# AQ_sensor_MRC.net
KiCad netlist of a schematic drawn in EAGLE
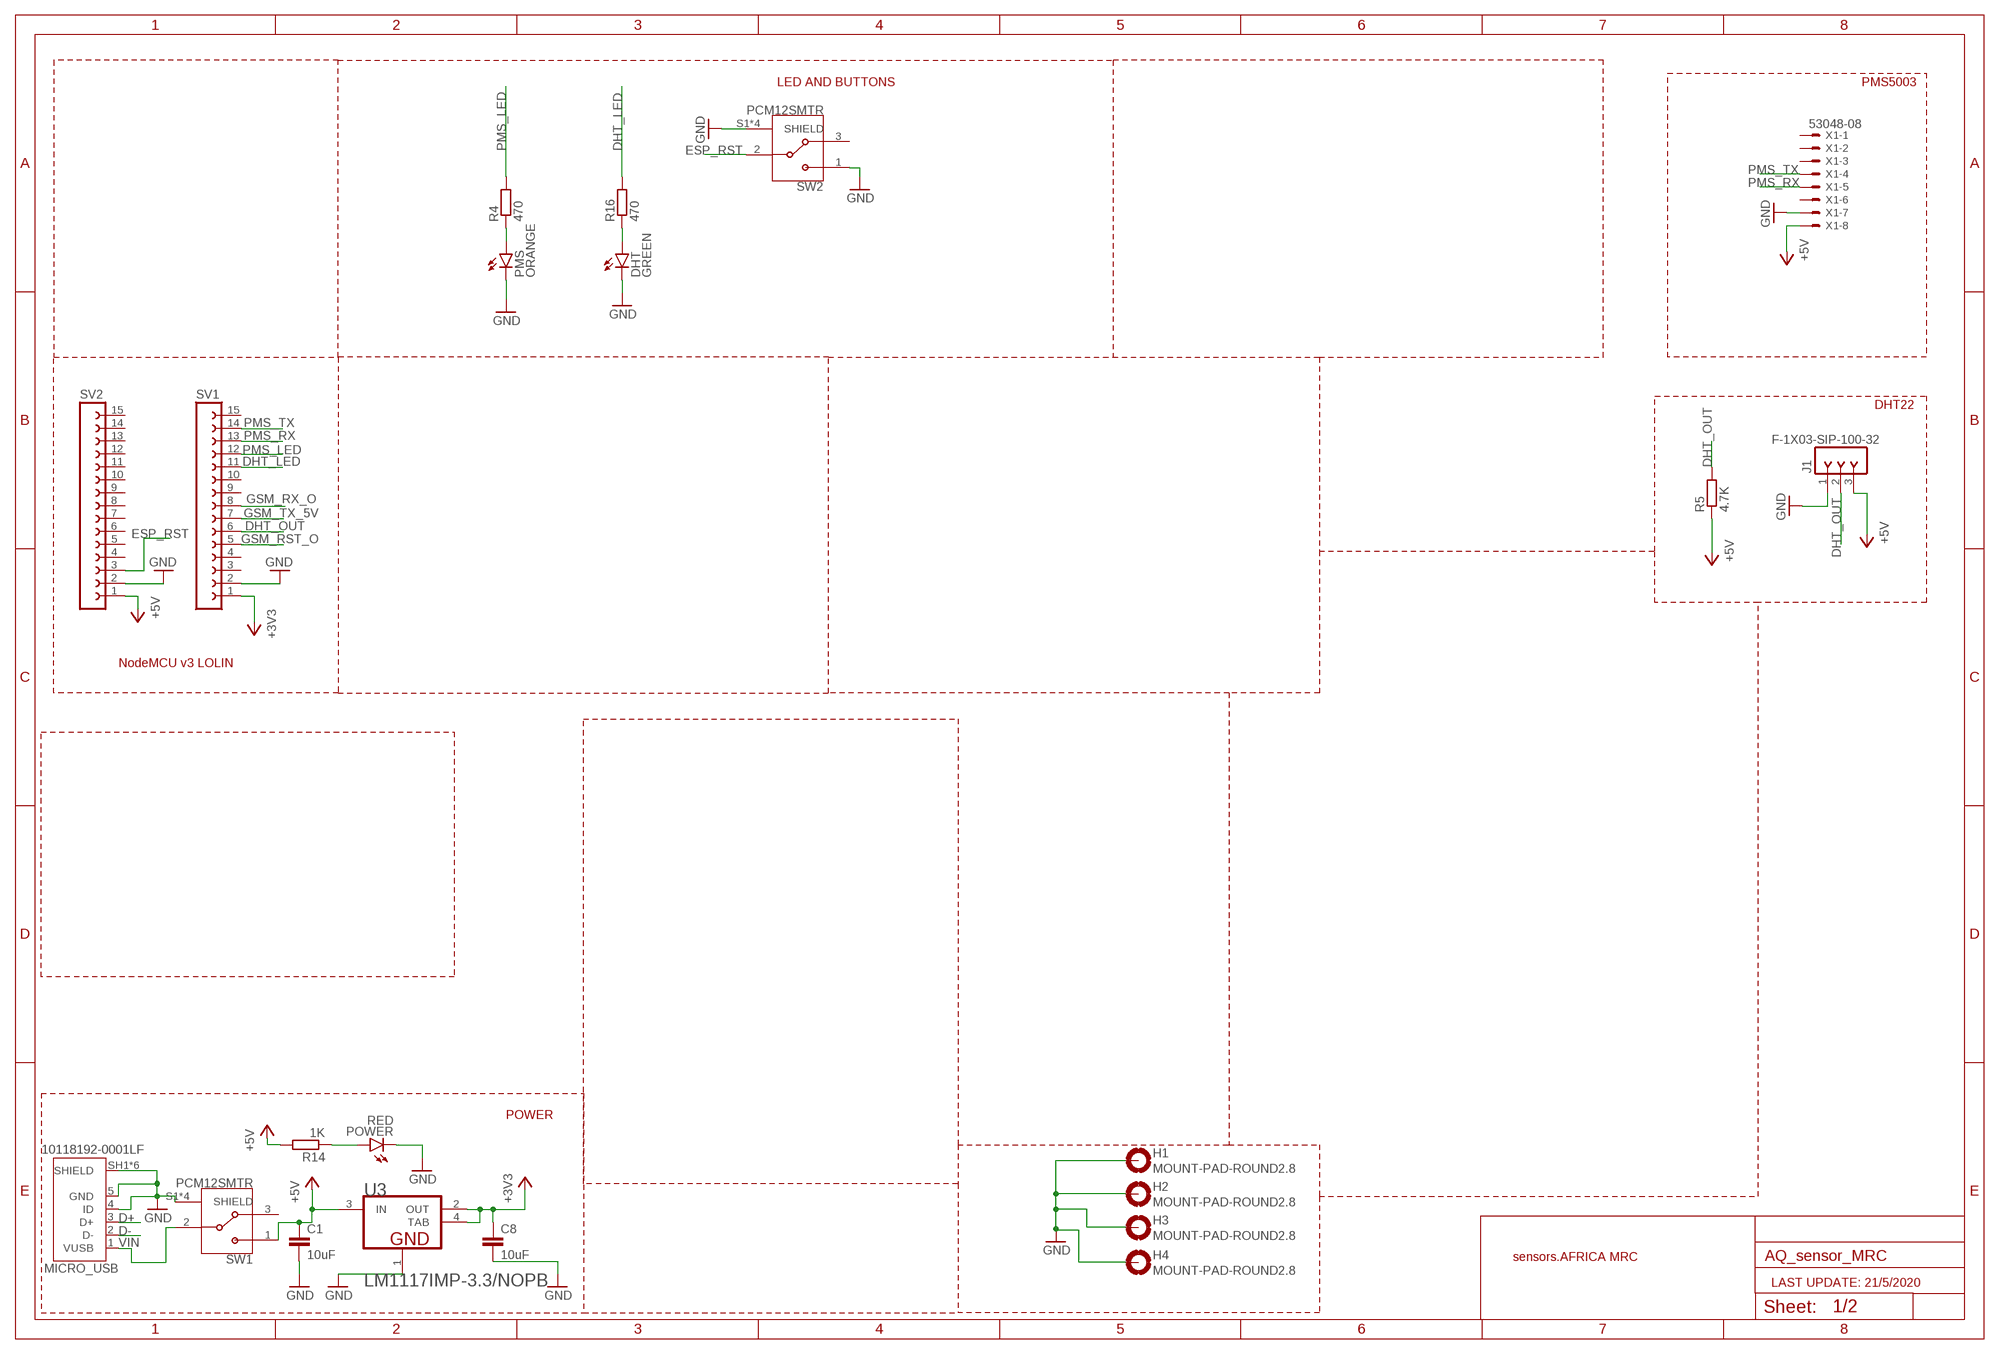
[diagram p0: schematic, sheet 1]
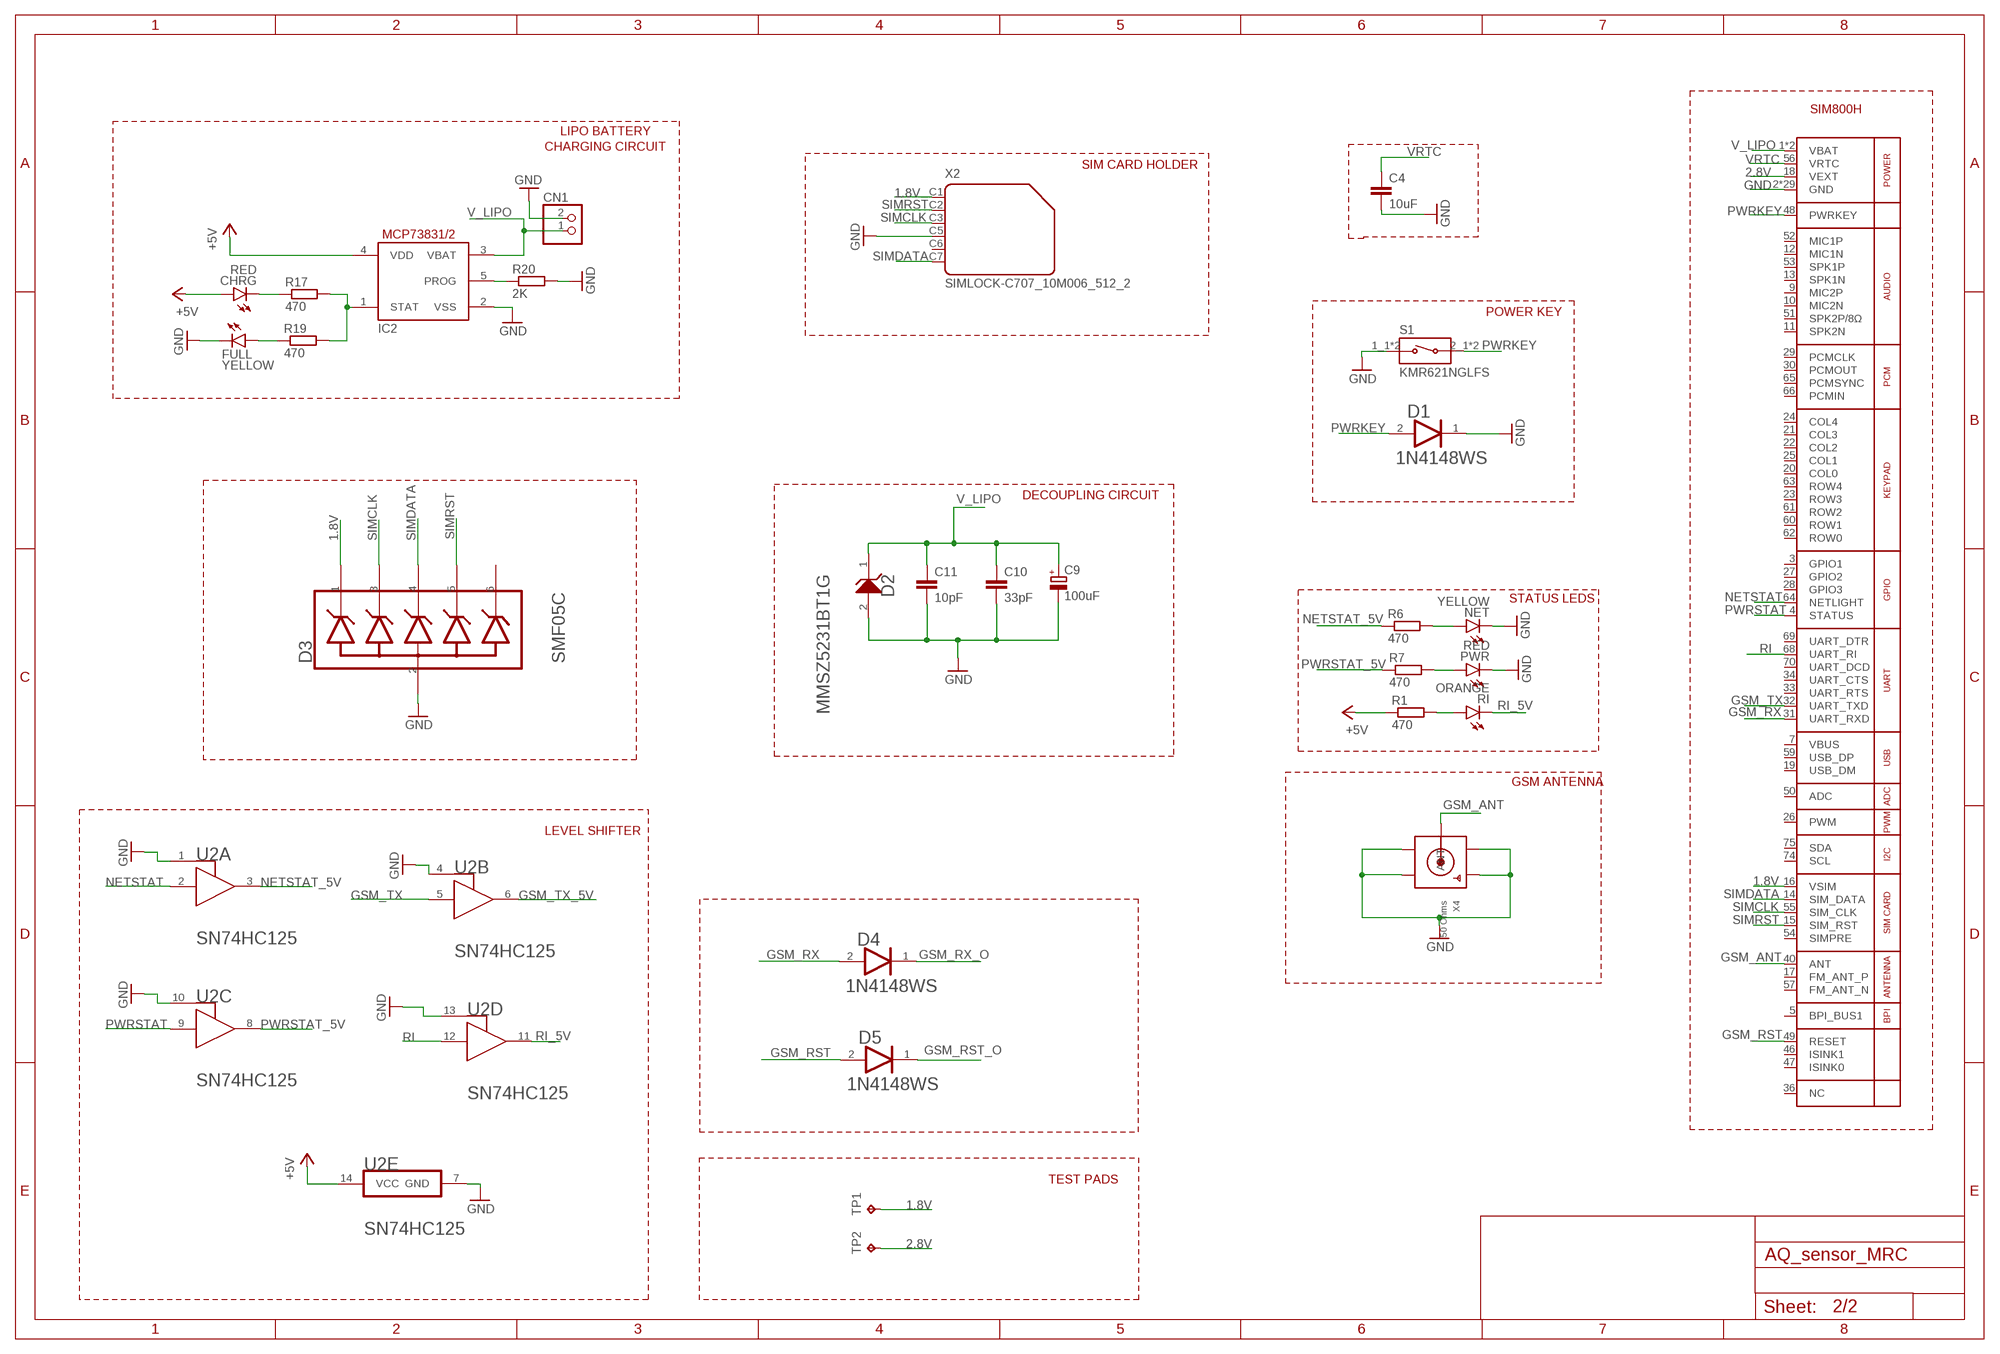
[diagram p1: schematic, sheet 2]

(export (version "E")
  (design (tool "Eeschema 10.0.6"))
  (components
    (comp (ref "C4")
      (value "10uF")
      (footprint "eagle-import:C0603")
      (libsource (lib "eagle-import") (part "C-EUC0603"))
    )
    (comp (ref "C9")
      (value "100uF")
      (footprint "eagle-import:PANASONIC_D")
      (libsource (lib "eagle-import") (part "CPOL-EUD"))
    )
    (comp (ref "C10")
      (value "33pF")
      (footprint "eagle-import:C0603")
      (libsource (lib "eagle-import") (part "C-EUC0603"))
    )
    (comp (ref "C11")
      (value "10pF")
      (footprint "eagle-import:C0603")
      (libsource (lib "eagle-import") (part "C-EUC0603"))
    )
    (comp (ref "CHRG")
      (value "RED")
      (footprint "eagle-import:CHIP-LED0603")
      (libsource (lib "eagle-import") (part "LEDCHIP-LED0603"))
    )
    (comp (ref "CN1")
      (value "JST_2PIN-SMT-RA")
      (footprint "eagle-import:JST-PH-2-SMT-RA")
      (libsource (lib "eagle-import") (part "JST_2PIN-SMT-RA"))
    )
    (comp (ref "D1")
      (value "ON_SEMI_1N4148WSON_SEMI_1N4148WS_0_0")
      (footprint "eagle-import:ON_SEMI_1N4148WS_0")
      (fields
        (field (name "DIGIKEY_PART_NUMBER") "1N4148WSFSCT-ND")
        (field (name "MF") "ON Semi")
        (field (name "MOUSER_PART_NUMBER") "512-1N4148WS")
      )
      (libsource (lib "eagle-import") (part "ON_SEMI_1N4148WSON_SEMI_1N4148WS_0_0"))
    )
    (comp (ref "D2")
      (value "ON_SEMICONDUCTOR_MMSZ5231BT1GON_SEMICONDUCTOR_MMSZ5231BT1G_0_0")
      (footprint "eagle-import:ON_SEMICONDUCTOR_MMSZ5231BT1G_0")
      (fields (field (name "MF") "On Semiconductor") (field (name "MPN") "MMSZ5231BT1G"))
      (libsource (lib "eagle-import") (part "ON_SEMICONDUCTOR_MMSZ5231BT1GON_SEMICONDUCTOR_MMSZ5231BT1G_0_0"))
    )
    (comp (ref "D3")
      (value "SEMTECH_SMF05CSEMTECH_SMF05C_0_0")
      (footprint "eagle-import:SEMTECH_SMF05C_0")
      (fields
        (field (name "DIGIKEY_PART_NUMBER") "SMF05CCT-ND")
        (field (name "MF") "Semtech")
        (field (name "MOUSER_PART_NUMBER") "947-SMF05C.TCT")
      )
      (libsource (lib "eagle-import") (part "SEMTECH_SMF05CSEMTECH_SMF05C_0_0"))
    )
    (comp (ref "D4")
      (value "ON_SEMI_1N4148WSON_SEMI_1N4148WS_0_0")
      (footprint "eagle-import:ON_SEMI_1N4148WS_0")
      (fields
        (field (name "DIGIKEY_PART_NUMBER") "1N4148WSFSCT-ND")
        (field (name "MF") "ON Semi")
        (field (name "MOUSER_PART_NUMBER") "512-1N4148WS")
      )
      (libsource (lib "eagle-import") (part "ON_SEMI_1N4148WSON_SEMI_1N4148WS_0_0"))
    )
    (comp (ref "D5")
      (value "ON_SEMI_1N4148WSON_SEMI_1N4148WS_0_0")
      (footprint "eagle-import:ON_SEMI_1N4148WS_0")
      (fields
        (field (name "DIGIKEY_PART_NUMBER") "1N4148WSFSCT-ND")
        (field (name "MF") "ON Semi")
        (field (name "MOUSER_PART_NUMBER") "512-1N4148WS")
      )
      (libsource (lib "eagle-import") (part "ON_SEMI_1N4148WSON_SEMI_1N4148WS_0_0"))
    )
    (comp (ref "FULL")
      (value "YELLOW")
      (footprint "eagle-import:CHIP-LED0603")
      (libsource (lib "eagle-import") (part "LEDCHIP-LED0603"))
    )
    (comp (ref "IC2")
      (value "MCP73831/OT")
      (footprint "eagle-import:SOT23-5L")
      (libsource (lib "eagle-import") (part "MCP73831/OT"))
    )
    (comp (ref "NET")
      (value "YELLOW")
      (footprint "eagle-import:CHIP-LED0603")
      (libsource (lib "eagle-import") (part "LEDCHIP-LED0603"))
    )
    (comp (ref "PWR")
      (value "RED")
      (footprint "eagle-import:CHIP-LED0603")
      (libsource (lib "eagle-import") (part "LEDCHIP-LED0603"))
    )
    (comp (ref "R1")
      (value "470")
      (footprint "eagle-import:R0603")
      (libsource (lib "eagle-import") (part "R-EU_R0603"))
    )
    (comp (ref "R6")
      (value "470")
      (footprint "eagle-import:R0603")
      (libsource (lib "eagle-import") (part "R-EU_R0603"))
    )
    (comp (ref "R7")
      (value "470")
      (footprint "eagle-import:R0603")
      (libsource (lib "eagle-import") (part "R-EU_R0603"))
    )
    (comp (ref "R17")
      (value "470")
      (footprint "eagle-import:R0603")
      (libsource (lib "eagle-import") (part "R-EU_R0603"))
    )
    (comp (ref "R19")
      (value "470")
      (footprint "eagle-import:R0603")
      (libsource (lib "eagle-import") (part "R-EU_R0603"))
    )
    (comp (ref "R20")
      (value "2K")
      (footprint "eagle-import:R0603")
      (libsource (lib "eagle-import") (part "R-EU_R0603"))
    )
    (comp (ref "RI")
      (value "ORANGE")
      (footprint "eagle-import:CHIP-LED0603")
      (libsource (lib "eagle-import") (part "LEDCHIP-LED0603"))
    )
    (comp (ref "S1")
      (value "KMR621NGLFS")
      (footprint "eagle-import:SW_KMR621NGLFS")
      (fields (field (name "MF") "C&K") (field (name "MP") "KMR621NG LFS"))
      (libsource (lib "eagle-import") (part "KMR621NGLFS"))
    )
    (comp (ref "TP1")
      (value "TPB1,27")
      (footprint "eagle-import:B1,27")
      (libsource (lib "eagle-import") (part "TPB1,27"))
    )
    (comp (ref "TP2")
      (value "TPB1,27")
      (footprint "eagle-import:B1,27")
      (libsource (lib "eagle-import") (part "TPB1,27"))
    )
    (comp (ref "U1")
      (value "GSM_SIM800L")
      (footprint "eagle-import:SIM800L")
      (libsource (lib "eagle-import") (part "GSM_SIM800L"))
    )
    (comp (ref "U2")
      (value "TEXAS_INSTRUMENTS_SN74HC125TEXAS_INSTRUMENTS_SN74HC125_0_0")
      (footprint "eagle-import:TEXAS_INSTRUMENTS_SN74HC125_0")
      (fields (field (name "MF") "Texas Instruments") (field (name "MPN") "SN74HC125"))
      (libsource (lib "eagle-import") (part "TEXAS_INSTRUMENTS_SN74HC125TEXAS_INSTRUMENTS_SN74HC125_0_0"))
    )
    (comp (ref "X2")
      (value "SIMLOCK-C707_10M006_512_2")
      (footprint "eagle-import:C707_10M006_512_2")
      (libsource (lib "eagle-import") (part "SIMLOCK-C707_10M006_512_2"))
    )
    (comp (ref "X4")
      (value "50 Ohms")
      (footprint "eagle-import:SMA_EDGELAUNCH_UFL")
      (libsource (lib "eagle-import") (part "SMACONNECTOR_EDGE_UFL"))
    )
    (comp (ref "C1")
      (value "10uF")
      (footprint "eagle-import:C0603")
      (libsource (lib "eagle-import") (part "C-EUC0603"))
    )
    (comp (ref "C8")
      (value "10uF")
      (footprint "eagle-import:C0603")
      (libsource (lib "eagle-import") (part "C-EUC0603"))
    )
    (comp (ref "DHT")
      (value "GREEN")
      (footprint "eagle-import:CHIP-LED0603")
      (libsource (lib "eagle-import") (part "LEDCHIP-LED0603"))
    )
    (comp (ref "H1")
      (value "MOUNT-PAD-ROUND2.8")
      (footprint "eagle-import:2,8-PAD")
      (libsource (lib "eagle-import") (part "MOUNT-PAD-ROUND2.8"))
    )
    (comp (ref "H2")
      (value "MOUNT-PAD-ROUND2.8")
      (footprint "eagle-import:2,8-PAD")
      (libsource (lib "eagle-import") (part "MOUNT-PAD-ROUND2.8"))
    )
    (comp (ref "H3")
      (value "MOUNT-PAD-ROUND2.8")
      (footprint "eagle-import:2,8-PAD")
      (libsource (lib "eagle-import") (part "MOUNT-PAD-ROUND2.8"))
    )
    (comp (ref "H4")
      (value "MOUNT-PAD-ROUND2.8")
      (footprint "eagle-import:2,8-PAD")
      (libsource (lib "eagle-import") (part "MOUNT-PAD-ROUND2.8"))
    )
    (comp (ref "J1")
      (value "F-1X03-SIP-100-32")
      (footprint "eagle-import:SIP-100-03-32")
      (libsource (lib "eagle-import") (part "F-1X03-SIP-100-32"))
    )
    (comp (ref "MICRO_USB")
      (value "10118192-0001LF")
      (footprint "eagle-import:AMPHENOL_10118192-0001LF")
      (fields (field (name "MF") "Amphenol ICC"))
      (libsource (lib "eagle-import") (part "10118192-0001LF"))
    )
    (comp (ref "PMS")
      (value "ORANGE")
      (footprint "eagle-import:CHIP-LED0603")
      (libsource (lib "eagle-import") (part "LEDCHIP-LED0603"))
    )
    (comp (ref "POWER")
      (value "RED")
      (footprint "eagle-import:CHIP-LED0603")
      (libsource (lib "eagle-import") (part "LEDCHIP-LED0603"))
    )
    (comp (ref "R4")
      (value "470")
      (footprint "eagle-import:R0603")
      (libsource (lib "eagle-import") (part "R-EU_R0603"))
    )
    (comp (ref "R5")
      (value "4.7K")
      (footprint "eagle-import:R0603")
      (libsource (lib "eagle-import") (part "R-EU_R0603"))
    )
    (comp (ref "R14")
      (value "1K")
      (footprint "eagle-import:R0603")
      (libsource (lib "eagle-import") (part "R-EU_R0603"))
    )
    (comp (ref "R16")
      (value "470")
      (footprint "eagle-import:R0603")
      (libsource (lib "eagle-import") (part "R-EU_R0603"))
    )
    (comp (ref "SV1")
      (value "FE15-1")
      (footprint "eagle-import:FE15")
      (libsource (lib "eagle-import") (part "FE15-1"))
    )
    (comp (ref "SV2")
      (value "FE15-1")
      (footprint "eagle-import:FE15")
      (libsource (lib "eagle-import") (part "FE15-1"))
    )
    (comp (ref "SW1")
      (value "PCM12SMTR")
      (footprint "eagle-import:SW_PCM12SMTR")
      (fields (field (name "MF") "C&K"))
      (libsource (lib "eagle-import") (part "PCM12SMTR"))
    )
    (comp (ref "SW2")
      (value "PCM12SMTR")
      (footprint "eagle-import:SW_PCM12SMTR")
      (fields (field (name "MF") "C&K"))
      (libsource (lib "eagle-import") (part "PCM12SMTR"))
    )
    (comp (ref "U3")
      (value "TEXAS_INSTRUMENTS_LM1117IMP-3.3-NOPBTEXAS_INSTRUMENTS_LM1117IMP-3.3-NOPB_0_0")
      (footprint "eagle-import:TEXAS_INSTRUMENTS_LM1117IMP-3.3-NOPB_0")
      (fields (field (name "MF") "Texas Instruments") (field (name "MPN") "LM1117IMP-3.3/NOPB"))
      (libsource (lib "eagle-import") (part "TEXAS_INSTRUMENTS_LM1117IMP-3.3-NOPBTEXAS_INSTRUMENTS_LM1117IMP-3.3-NOPB_0_0"))
    )
    (comp (ref "X1")
      (value "53048-08")
      (footprint "eagle-import:53048-08")
      (fields (field (name "MF") "WALDOM/MOLEX") (field (name "MPN") "53048-0810"))
      (libsource (lib "eagle-import") (part "53?-08048"))
    )
  )
  (nets
    (net (code "1") (name "+3V3") (class "Default")
      (node (ref "C8") (pin "1") (pinfunction "1_1") (pintype "passive"))
      (node (ref "SV1") (pin "1") (pinfunction "1_1") (pintype "passive"))
      (node (ref "U3") (pin "2") (pinfunction "OUT_2") (pintype "power_in"))
      (node (ref "U3") (pin "4") (pinfunction "TAB_4") (pintype "power_in"))
    )
    (net (code "2") (name "+5V") (class "Default")
      (node (ref "C1") (pin "1") (pinfunction "1_1") (pintype "passive"))
      (node (ref "CHRG") (pin "A") (pinfunction "A_A") (pintype "passive"))
      (node (ref "IC2") (pin "4") (pinfunction "VDD_4") (pintype "power_in"))
      (node (ref "J1") (pin "3") (pinfunction "3_3") (pintype "passive"))
      (node (ref "R1") (pin "1") (pinfunction "1_1") (pintype "passive"))
      (node (ref "R14") (pin "2") (pinfunction "2_2") (pintype "passive"))
      (node (ref "R5") (pin "1") (pinfunction "1_1") (pintype "passive"))
      (node (ref "SV2") (pin "1") (pinfunction "1_1") (pintype "passive"))
      (node (ref "SW1") (pin "1") (pinfunction "1_1") (pintype "passive"))
      (node (ref "U2") (pin "14") (pinfunction "VCC_14") (pintype "power_in"))
      (node (ref "U3") (pin "3") (pinfunction "IN_3") (pintype "power_in"))
      (node (ref "X1") (pin "8") (pinfunction "S_8") (pintype "passive"))
    )
    (net (code "3") (name "1.8V") (class "Default")
      (node (ref "D3") (pin "1") (pinfunction "1_CATHODE_1") (pintype "bidirectional"))
      (node (ref "TP1") (pin "TP") (pinfunction "TP_TP") (pintype "input"))
      (node (ref "U1") (pin "16") (pinfunction "VSIM_16") (pintype "power_in"))
      (node (ref "X2") (pin "C1") (pinfunction "1_C1") (pintype "passive"))
    )
    (net (code "4") (name "2.8V") (class "Default")
      (node (ref "TP2") (pin "TP") (pinfunction "TP_TP") (pintype "input"))
      (node (ref "U1") (pin "18") (pinfunction "VEXT_18") (pintype "power_in"))
    )
    (net (code "5") (name "D+") (class "Default")
      (node (ref "MICRO_USB") (pin "3") (pinfunction "D+_3") (pintype "passive"))
    )
    (net (code "6") (name "D-") (class "Default")
      (node (ref "MICRO_USB") (pin "2") (pinfunction "D-_2") (pintype "passive"))
    )
    (net (code "7") (name "DHT_LED") (class "Default")
      (node (ref "R16") (pin "2") (pinfunction "2_2") (pintype "passive"))
      (node (ref "SV1") (pin "11") (pinfunction "11_11") (pintype "passive"))
    )
    (net (code "8") (name "DHT_OUT") (class "Default")
      (node (ref "J1") (pin "2") (pinfunction "2_2") (pintype "passive"))
      (node (ref "R5") (pin "2") (pinfunction "2_2") (pintype "passive"))
      (node (ref "SV1") (pin "6") (pinfunction "6_6") (pintype "passive"))
    )
    (net (code "9") (name "ESP_RST") (class "Default")
      (node (ref "SV2") (pin "3") (pinfunction "3_3") (pintype "passive"))
      (node (ref "SW2") (pin "2") (pinfunction "2_2") (pintype "passive"))
    )
    (net (code "10") (name "GND") (class "Default")
      (node (ref "C1") (pin "2") (pinfunction "2_2") (pintype "passive"))
      (node (ref "C10") (pin "2") (pinfunction "2_2") (pintype "passive"))
      (node (ref "C11") (pin "2") (pinfunction "2_2") (pintype "passive"))
      (node (ref "C4") (pin "2") (pinfunction "2_2") (pintype "passive"))
      (node (ref "C8") (pin "2") (pinfunction "2_2") (pintype "passive"))
      (node (ref "C9") (pin "-") (pinfunction "-_-") (pintype "passive"))
      (node (ref "CN1") (pin "2") (pinfunction "1_2") (pintype "passive"))
      (node (ref "D1") (pin "1") (pinfunction "CATHODE_1") (pintype "bidirectional"))
      (node (ref "D2") (pin "2") (pinfunction "A_2") (pintype "passive"))
      (node (ref "D3") (pin "2") (pinfunction "ANODE_2") (pintype "bidirectional"))
      (node (ref "DHT") (pin "C") (pinfunction "C_C") (pintype "passive"))
      (node (ref "FULL") (pin "C") (pinfunction "C_C") (pintype "passive"))
      (node (ref "H1") (pin "B2,8") (pinfunction "MOUNT_B2,8") (pintype "passive"))
      (node (ref "H2") (pin "B2,8") (pinfunction "MOUNT_B2,8") (pintype "passive"))
      (node (ref "H3") (pin "B2,8") (pinfunction "MOUNT_B2,8") (pintype "passive"))
      (node (ref "H4") (pin "B2,8") (pinfunction "MOUNT_B2,8") (pintype "passive"))
      (node (ref "IC2") (pin "2") (pinfunction "VSS_2") (pintype "power_in"))
      (node (ref "J1") (pin "1") (pinfunction "1_1") (pintype "passive"))
      (node (ref "MICRO_USB") (pin "4") (pinfunction "ID_4") (pintype "passive"))
      (node (ref "MICRO_USB") (pin "5") (pinfunction "GND_5") (pintype "passive"))
      (node (ref "MICRO_USB") (pin "SH1") (pinfunction "SHIELD_SH1") (pintype "passive"))
      (node (ref "MICRO_USB") (pin "SH2") (pinfunction "SHIELD_SH2") (pintype "passive"))
      (node (ref "MICRO_USB") (pin "SH3") (pinfunction "SHIELD_SH3") (pintype "passive"))
      (node (ref "MICRO_USB") (pin "SH4") (pinfunction "SHIELD_SH4") (pintype "passive"))
      (node (ref "MICRO_USB") (pin "SH5") (pinfunction "SHIELD_SH5") (pintype "passive"))
      (node (ref "MICRO_USB") (pin "SH6") (pinfunction "SHIELD_SH6") (pintype "passive"))
      (node (ref "NET") (pin "C") (pinfunction "C_C") (pintype "passive"))
      (node (ref "PMS") (pin "C") (pinfunction "C_C") (pintype "passive"))
      (node (ref "POWER") (pin "C") (pinfunction "C_C") (pintype "passive"))
      (node (ref "PWR") (pin "C") (pinfunction "C_C") (pintype "passive"))
      (node (ref "R20") (pin "2") (pinfunction "2_2") (pintype "passive"))
      (node (ref "S1") (pin "1_1") (pinfunction "1_1_1") (pintype "passive"))
      (node (ref "S1") (pin "1_2") (pinfunction "1_1_2") (pintype "passive"))
      (node (ref "SV1") (pin "2") (pinfunction "2_2") (pintype "passive"))
      (node (ref "SV2") (pin "2") (pinfunction "2_2") (pintype "passive"))
      (node (ref "SW1") (pin "S1") (pinfunction "SHIELD_S1") (pintype "passive"))
      (node (ref "SW1") (pin "S2") (pinfunction "SHIELD_S2") (pintype "passive"))
      (node (ref "SW1") (pin "S3") (pinfunction "SHIELD_S3") (pintype "passive"))
      (node (ref "SW1") (pin "S4") (pinfunction "SHIELD_S4") (pintype "passive"))
      (node (ref "SW2") (pin "1") (pinfunction "1_1") (pintype "passive"))
      (node (ref "SW2") (pin "S1") (pinfunction "SHIELD_S1") (pintype "passive"))
      (node (ref "SW2") (pin "S2") (pinfunction "SHIELD_S2") (pintype "passive"))
      (node (ref "SW2") (pin "S3") (pinfunction "SHIELD_S3") (pintype "passive"))
      (node (ref "SW2") (pin "S4") (pinfunction "SHIELD_S4") (pintype "passive"))
      (node (ref "U1") (pin "2") (pinfunction "GND_2") (pintype "power_in"))
      (node (ref "U1") (pin "35") (pinfunction "GND_35") (pintype "power_in"))
      (node (ref "U1") (pin "37") (pinfunction "GND_37") (pintype "power_in"))
      (node (ref "U1") (pin "38") (pinfunction "GND_38") (pintype "power_in"))
      (node (ref "U1") (pin "39") (pinfunction "GND_39") (pintype "power_in"))
      (node (ref "U1") (pin "41") (pinfunction "GND_41") (pintype "power_in"))
      (node (ref "U1") (pin "43") (pinfunction "GND_43") (pintype "power_in"))
      (node (ref "U1") (pin "44") (pinfunction "GND_44") (pintype "power_in"))
      (node (ref "U1") (pin "45") (pinfunction "GND_45") (pintype "power_in"))
      (node (ref "U1") (pin "58") (pinfunction "GND_58") (pintype "power_in"))
      (node (ref "U1") (pin "6") (pinfunction "GND_6") (pintype "power_in"))
      (node (ref "U1") (pin "67") (pinfunction "GND_67") (pintype "power_in"))
      (node (ref "U1") (pin "71") (pinfunction "GND_71") (pintype "power_in"))
      (node (ref "U1") (pin "72") (pinfunction "GND_72") (pintype "power_in"))
      (node (ref "U1") (pin "73") (pinfunction "GND_73") (pintype "power_in"))
      (node (ref "U1") (pin "76") (pinfunction "GND_76") (pintype "power_in"))
      (node (ref "U1") (pin "77") (pinfunction "GND_77") (pintype "power_in"))
      (node (ref "U1") (pin "78") (pinfunction "GND_78") (pintype "power_in"))
      (node (ref "U1") (pin "79") (pinfunction "GND_79") (pintype "power_in"))
      (node (ref "U1") (pin "8") (pinfunction "GND_8") (pintype "power_in"))
      (node (ref "U1") (pin "80") (pinfunction "GND_80") (pintype "power_in"))
      (node (ref "U1") (pin "81") (pinfunction "GND_81") (pintype "power_in"))
      (node (ref "U1") (pin "82") (pinfunction "GND_82") (pintype "power_in"))
      (node (ref "U1") (pin "83") (pinfunction "GND_83") (pintype "power_in"))
      (node (ref "U1") (pin "84") (pinfunction "GND_84") (pintype "power_in"))
      (node (ref "U1") (pin "85") (pinfunction "GND_85") (pintype "power_in"))
      (node (ref "U1") (pin "86") (pinfunction "GND_86") (pintype "power_in"))
      (node (ref "U1") (pin "87") (pinfunction "GND_87") (pintype "power_in"))
      (node (ref "U1") (pin "88") (pinfunction "GND_88") (pintype "power_in"))
      (node (ref "U2") (pin "1") (pinfunction "1_~{OE}_1") (pintype "input"))
      (node (ref "U2") (pin "10") (pinfunction "2_~{OE}_10") (pintype "input"))
      (node (ref "U2") (pin "13") (pinfunction "3_~{OE}_13") (pintype "input"))
      (node (ref "U2") (pin "4") (pinfunction "4_~{OE}_4") (pintype "input"))
      (node (ref "U2") (pin "7") (pinfunction "GND_7") (pintype "power_in"))
      (node (ref "U3") (pin "1") (pinfunction "GND_1") (pintype "power_in"))
      (node (ref "X1") (pin "7") (pinfunction "S_7") (pintype "passive"))
      (node (ref "X2") (pin "C5") (pinfunction "4_C5") (pintype "passive"))
      (node (ref "X4") (pin "GND@1") (pinfunction "GND1_GND@1") (pintype "power_in"))
      (node (ref "X4") (pin "GND@2") (pinfunction "GND2_GND@2") (pintype "power_in"))
      (node (ref "X4") (pin "GND@3") (pinfunction "GND3_GND@3") (pintype "power_in"))
      (node (ref "X4") (pin "GND@4") (pinfunction "GND4_GND@4") (pintype "power_in"))
    )
    (net (code "11") (name "GSM_ANT") (class "Default")
      (node (ref "U1") (pin "40") (pinfunction "ANT_40") (pintype "bidirectional"))
      (node (ref "X4") (pin "P") (pinfunction "ANT_P") (pintype "bidirectional"))
    )
    (net (code "12") (name "GSM_RST") (class "Default")
      (node (ref "D5") (pin "2") (pinfunction "ANODE_2") (pintype "bidirectional"))
      (node (ref "U1") (pin "49") (pinfunction "RESET_49") (pintype "input"))
    )
    (net (code "13") (name "GSM_RST_O") (class "Default")
      (node (ref "D5") (pin "1") (pinfunction "CATHODE_1") (pintype "bidirectional"))
      (node (ref "SV1") (pin "5") (pinfunction "5_5") (pintype "passive"))
    )
    (net (code "14") (name "GSM_RX") (class "Default")
      (node (ref "D4") (pin "2") (pinfunction "ANODE_2") (pintype "bidirectional"))
      (node (ref "U1") (pin "31") (pinfunction "UART_RXD_31") (pintype "input"))
    )
    (net (code "15") (name "GSM_RX_O") (class "Default")
      (node (ref "D4") (pin "1") (pinfunction "CATHODE_1") (pintype "bidirectional"))
      (node (ref "SV1") (pin "8") (pinfunction "8_8") (pintype "passive"))
    )
    (net (code "16") (name "GSM_TX") (class "Default")
      (node (ref "U1") (pin "32") (pinfunction "UART_TXD_32") (pintype "output"))
      (node (ref "U2") (pin "5") (pinfunction "2A_5") (pintype "input"))
    )
    (net (code "17") (name "GSM_TX_5V") (class "Default")
      (node (ref "SV1") (pin "7") (pinfunction "7_7") (pintype "passive"))
      (node (ref "U2") (pin "6") (pinfunction "2Y_6") (pintype "tri_state"))
    )
    (net (code "18") (name "NETSTAT") (class "Default")
      (node (ref "U1") (pin "64") (pinfunction "NETLIGHT_64") (pintype "output"))
      (node (ref "U2") (pin "2") (pinfunction "1A_2") (pintype "input"))
    )
    (net (code "19") (name "NETSTAT_5V") (class "Default")
      (node (ref "R6") (pin "1") (pinfunction "1_1") (pintype "passive"))
      (node (ref "U2") (pin "3") (pinfunction "1Y_3") (pintype "tri_state"))
    )
    (net (code "20") (name "Net-(CHRG-PadC)") (class "Default")
      (node (ref "CHRG") (pin "C") (pinfunction "C_C") (pintype "passive"))
      (node (ref "R17") (pin "1") (pinfunction "1_1") (pintype "passive"))
    )
    (net (code "21") (name "Net-(DHT-PadA)") (class "Default")
      (node (ref "DHT") (pin "A") (pinfunction "A_A") (pintype "passive"))
      (node (ref "R16") (pin "1") (pinfunction "1_1") (pintype "passive"))
    )
    (net (code "22") (name "Net-(FULL-PadA)") (class "Default")
      (node (ref "FULL") (pin "A") (pinfunction "A_A") (pintype "passive"))
      (node (ref "R19") (pin "1") (pinfunction "1_1") (pintype "passive"))
    )
    (net (code "23") (name "Net-(IC2-PROG)") (class "Default")
      (node (ref "IC2") (pin "5") (pinfunction "PROG_5") (pintype "input"))
      (node (ref "R20") (pin "1") (pinfunction "1_1") (pintype "passive"))
    )
    (net (code "24") (name "Net-(IC2-STAT)") (class "Default")
      (node (ref "IC2") (pin "1") (pinfunction "STAT_1") (pintype "output"))
      (node (ref "R17") (pin "2") (pinfunction "2_2") (pintype "passive"))
      (node (ref "R19") (pin "2") (pinfunction "2_2") (pintype "passive"))
    )
    (net (code "25") (name "Net-(NET-PadA)") (class "Default")
      (node (ref "NET") (pin "A") (pinfunction "A_A") (pintype "passive"))
      (node (ref "R6") (pin "2") (pinfunction "2_2") (pintype "passive"))
    )
    (net (code "26") (name "Net-(PMS-PadA)") (class "Default")
      (node (ref "PMS") (pin "A") (pinfunction "A_A") (pintype "passive"))
      (node (ref "R4") (pin "1") (pinfunction "1_1") (pintype "passive"))
    )
    (net (code "27") (name "Net-(POWER-PadA)") (class "Default")
      (node (ref "POWER") (pin "A") (pinfunction "A_A") (pintype "passive"))
      (node (ref "R14") (pin "1") (pinfunction "1_1") (pintype "passive"))
    )
    (net (code "28") (name "Net-(PWR-PadA)") (class "Default")
      (node (ref "PWR") (pin "A") (pinfunction "A_A") (pintype "passive"))
      (node (ref "R7") (pin "2") (pinfunction "2_2") (pintype "passive"))
    )
    (net (code "29") (name "Net-(R1-Pad2)") (class "Default")
      (node (ref "R1") (pin "2") (pinfunction "2_2") (pintype "passive"))
      (node (ref "RI") (pin "A") (pinfunction "A_A") (pintype "passive"))
    )
    (net (code "30") (name "PMS_LED") (class "Default")
      (node (ref "R4") (pin "2") (pinfunction "2_2") (pintype "passive"))
      (node (ref "SV1") (pin "12") (pinfunction "12_12") (pintype "passive"))
    )
    (net (code "31") (name "PMS_RX") (class "Default")
      (node (ref "SV1") (pin "13") (pinfunction "13_13") (pintype "passive"))
      (node (ref "X1") (pin "5") (pinfunction "S_5") (pintype "passive"))
    )
    (net (code "32") (name "PMS_TX") (class "Default")
      (node (ref "SV1") (pin "14") (pinfunction "14_14") (pintype "passive"))
      (node (ref "X1") (pin "4") (pinfunction "S_4") (pintype "passive"))
    )
    (net (code "33") (name "PWRKEY") (class "Default")
      (node (ref "D1") (pin "2") (pinfunction "ANODE_2") (pintype "bidirectional"))
      (node (ref "S1") (pin "2_1") (pinfunction "2_2_1") (pintype "passive"))
      (node (ref "S1") (pin "2_2") (pinfunction "2_2_2") (pintype "passive"))
      (node (ref "U1") (pin "48") (pinfunction "PWRKEY_48") (pintype "input"))
    )
    (net (code "34") (name "PWRSTAT") (class "Default")
      (node (ref "U1") (pin "4") (pinfunction "STATUS_4") (pintype "output"))
      (node (ref "U2") (pin "9") (pinfunction "3A_9") (pintype "input"))
    )
    (net (code "35") (name "PWRSTAT_5V") (class "Default")
      (node (ref "R7") (pin "1") (pinfunction "1_1") (pintype "passive"))
      (node (ref "U2") (pin "8") (pinfunction "3Y_8") (pintype "tri_state"))
    )
    (net (code "36") (name "RI") (class "Default")
      (node (ref "U1") (pin "68") (pinfunction "UART_RI_68") (pintype "output"))
      (node (ref "U2") (pin "12") (pinfunction "4A_12") (pintype "input"))
    )
    (net (code "37") (name "RI_5V") (class "Default")
      (node (ref "RI") (pin "C") (pinfunction "C_C") (pintype "passive"))
      (node (ref "U2") (pin "11") (pinfunction "4Y_11") (pintype "tri_state"))
    )
    (net (code "38") (name "SIMCLK") (class "Default")
      (node (ref "D3") (pin "3") (pinfunction "2_CATHODE_3") (pintype "bidirectional"))
      (node (ref "U1") (pin "55") (pinfunction "SIM_CLK_55") (pintype "output"))
      (node (ref "X2") (pin "C3") (pinfunction "3_C3") (pintype "passive"))
    )
    (net (code "39") (name "SIMDATA") (class "Default")
      (node (ref "D3") (pin "4") (pinfunction "3_CATHODE_4") (pintype "bidirectional"))
      (node (ref "U1") (pin "14") (pinfunction "SIM_DATA_14") (pintype "bidirectional"))
      (node (ref "X2") (pin "C7") (pinfunction "6_C7") (pintype "passive"))
    )
    (net (code "40") (name "SIMRST") (class "Default")
      (node (ref "D3") (pin "5") (pinfunction "4_CATHODE_5") (pintype "bidirectional"))
      (node (ref "U1") (pin "15") (pinfunction "SIM_RST_15") (pintype "output"))
      (node (ref "X2") (pin "C2") (pinfunction "2_C2") (pintype "passive"))
    )
    (net (code "41") (name "VBUS") (class "Default")
      (node (ref "U1") (pin "7") (pinfunction "VBUS_7") (pintype "power_in"))
    )
    (net (code "42") (name "VIN") (class "Default")
      (node (ref "MICRO_USB") (pin "1") (pinfunction "VUSB_1") (pintype "passive"))
      (node (ref "SW1") (pin "2") (pinfunction "2_2") (pintype "passive"))
    )
    (net (code "43") (name "VRTC") (class "Default")
      (node (ref "C4") (pin "1") (pinfunction "1_1") (pintype "passive"))
      (node (ref "U1") (pin "56") (pinfunction "VRTC_56") (pintype "power_in"))
    )
    (net (code "44") (name "V_LIPO") (class "Default")
      (node (ref "C10") (pin "1") (pinfunction "1_1") (pintype "passive"))
      (node (ref "C11") (pin "1") (pinfunction "1_1") (pintype "passive"))
      (node (ref "C9") (pin "+") (pinfunction "+_+") (pintype "passive"))
      (node (ref "CN1") (pin "1") (pinfunction "2_1") (pintype "passive"))
      (node (ref "D2") (pin "1") (pinfunction "K_1") (pintype "passive"))
      (node (ref "IC2") (pin "3") (pinfunction "VBAT_3") (pintype "bidirectional"))
      (node (ref "U1") (pin "1") (pinfunction "VBAT_1") (pintype "power_in"))
      (node (ref "U1") (pin "42") (pinfunction "VBAT_42") (pintype "power_in"))
    )
    (net (code "45") (name "unconnected-(D3-5_CATHODE-Pad6)") (class "Default")
      (node (ref "D3") (pin "6") (pinfunction "5_CATHODE_6") (pintype "bidirectional"))
    )
    (net (code "46") (name "unconnected-(SV1-Pad3)") (class "Default")
      (node (ref "SV1") (pin "3") (pinfunction "3_3") (pintype "passive"))
    )
    (net (code "47") (name "unconnected-(SV1-Pad4)") (class "Default")
      (node (ref "SV1") (pin "4") (pinfunction "4_4") (pintype "passive"))
    )
    (net (code "48") (name "unconnected-(SV1-Pad9)") (class "Default")
      (node (ref "SV1") (pin "9") (pinfunction "9_9") (pintype "passive"))
    )
    (net (code "49") (name "unconnected-(SV1-Pad10)") (class "Default")
      (node (ref "SV1") (pin "10") (pinfunction "10_10") (pintype "passive"))
    )
    (net (code "50") (name "unconnected-(SV1-Pad15)") (class "Default")
      (node (ref "SV1") (pin "15") (pinfunction "15_15") (pintype "passive"))
    )
    (net (code "51") (name "unconnected-(SV2-Pad4)") (class "Default")
      (node (ref "SV2") (pin "4") (pinfunction "4_4") (pintype "passive"))
    )
    (net (code "52") (name "unconnected-(SV2-Pad5)") (class "Default")
      (node (ref "SV2") (pin "5") (pinfunction "5_5") (pintype "passive"))
    )
    (net (code "53") (name "unconnected-(SV2-Pad6)") (class "Default")
      (node (ref "SV2") (pin "6") (pinfunction "6_6") (pintype "passive"))
    )
    (net (code "54") (name "unconnected-(SV2-Pad7)") (class "Default")
      (node (ref "SV2") (pin "7") (pinfunction "7_7") (pintype "passive"))
    )
    (net (code "55") (name "unconnected-(SV2-Pad8)") (class "Default")
      (node (ref "SV2") (pin "8") (pinfunction "8_8") (pintype "passive"))
    )
    (net (code "56") (name "unconnected-(SV2-Pad9)") (class "Default")
      (node (ref "SV2") (pin "9") (pinfunction "9_9") (pintype "passive"))
    )
    (net (code "57") (name "unconnected-(SV2-Pad10)") (class "Default")
      (node (ref "SV2") (pin "10") (pinfunction "10_10") (pintype "passive"))
    )
    (net (code "58") (name "unconnected-(SV2-Pad11)") (class "Default")
      (node (ref "SV2") (pin "11") (pinfunction "11_11") (pintype "passive"))
    )
    (net (code "59") (name "unconnected-(SV2-Pad12)") (class "Default")
      (node (ref "SV2") (pin "12") (pinfunction "12_12") (pintype "passive"))
    )
    (net (code "60") (name "unconnected-(SV2-Pad13)") (class "Default")
      (node (ref "SV2") (pin "13") (pinfunction "13_13") (pintype "passive"))
    )
    (net (code "61") (name "unconnected-(SV2-Pad14)") (class "Default")
      (node (ref "SV2") (pin "14") (pinfunction "14_14") (pintype "passive"))
    )
    (net (code "62") (name "unconnected-(SV2-Pad15)") (class "Default")
      (node (ref "SV2") (pin "15") (pinfunction "15_15") (pintype "passive"))
    )
    (net (code "63") (name "unconnected-(SW1-Pad3)") (class "Default")
      (node (ref "SW1") (pin "3") (pinfunction "3_3") (pintype "passive"))
    )
    (net (code "64") (name "unconnected-(SW2-Pad3)") (class "Default")
      (node (ref "SW2") (pin "3") (pinfunction "3_3") (pintype "passive"))
    )
    (net (code "65") (name "unconnected-(U1-ADC-Pad50)") (class "Default")
      (node (ref "U1") (pin "50") (pinfunction "ADC_50") (pintype "input"))
    )
    (net (code "66") (name "unconnected-(U1-BPI_BUS1-Pad5)") (class "Default")
      (node (ref "U1") (pin "5") (pinfunction "BPI_BUS1_5") (pintype "output"))
    )
    (net (code "67") (name "unconnected-(U1-COL0-Pad20)") (class "Default")
      (node (ref "U1") (pin "20") (pinfunction "COL0_20") (pintype "bidirectional"))
    )
    (net (code "68") (name "unconnected-(U1-COL1-Pad25)") (class "Default")
      (node (ref "U1") (pin "25") (pinfunction "COL1_25") (pintype "bidirectional"))
    )
    (net (code "69") (name "unconnected-(U1-COL2-Pad22)") (class "Default")
      (node (ref "U1") (pin "22") (pinfunction "COL2_22") (pintype "bidirectional"))
    )
    (net (code "70") (name "unconnected-(U1-COL3-Pad21)") (class "Default")
      (node (ref "U1") (pin "21") (pinfunction "COL3_21") (pintype "bidirectional"))
    )
    (net (code "71") (name "unconnected-(U1-COL4-Pad24)") (class "Default")
      (node (ref "U1") (pin "24") (pinfunction "COL4_24") (pintype "bidirectional"))
    )
    (net (code "72") (name "unconnected-(U1-FM_ANT_N-Pad57)") (class "Default")
      (node (ref "U1") (pin "57") (pinfunction "FM_ANT_N_57") (pintype "bidirectional"))
    )
    (net (code "73") (name "unconnected-(U1-FM_ANT_P-Pad17)") (class "Default")
      (node (ref "U1") (pin "17") (pinfunction "FM_ANT_P_17") (pintype "bidirectional"))
    )
    (net (code "74") (name "unconnected-(U1-GPIO1-Pad3)") (class "Default")
      (node (ref "U1") (pin "3") (pinfunction "GPIO1_3") (pintype "bidirectional"))
    )
    (net (code "75") (name "unconnected-(U1-GPIO2-Pad27)") (class "Default")
      (node (ref "U1") (pin "27") (pinfunction "GPIO2_27") (pintype "bidirectional"))
    )
    (net (code "76") (name "unconnected-(U1-GPIO3-Pad28)") (class "Default")
      (node (ref "U1") (pin "28") (pinfunction "GPIO3_28") (pintype "bidirectional"))
    )
    (net (code "77") (name "unconnected-(U1-ISINK0-Pad47)") (class "Default")
      (node (ref "U1") (pin "47") (pinfunction "ISINK0_47") (pintype "input"))
    )
    (net (code "78") (name "unconnected-(U1-ISINK1-Pad46)") (class "Default")
      (node (ref "U1") (pin "46") (pinfunction "ISINK1_46") (pintype "input"))
    )
    (net (code "79") (name "unconnected-(U1-MIC1N-Pad12)") (class "Default")
      (node (ref "U1") (pin "12") (pinfunction "MIC1N_12") (pintype "input"))
    )
    (net (code "80") (name "unconnected-(U1-MIC1P-Pad52)") (class "Default")
      (node (ref "U1") (pin "52") (pinfunction "MIC1P_52") (pintype "input"))
    )
    (net (code "81") (name "unconnected-(U1-MIC2N-Pad10)") (class "Default")
      (node (ref "U1") (pin "10") (pinfunction "MIC2N_10") (pintype "input"))
    )
    (net (code "82") (name "unconnected-(U1-MIC2P-Pad9)") (class "Default")
      (node (ref "U1") (pin "9") (pinfunction "MIC2P_9") (pintype "input"))
    )
    (net (code "83") (name "unconnected-(U1-NC-Pad36)") (class "Default")
      (node (ref "U1") (pin "36") (pinfunction "NC_36") (pintype "no_connect"))
    )
    (net (code "84") (name "unconnected-(U1-PCMCLK-Pad29)") (class "Default")
      (node (ref "U1") (pin "29") (pinfunction "PCMCLK_29") (pintype "output"))
    )
    (net (code "85") (name "unconnected-(U1-PCMIN-Pad66)") (class "Default")
      (node (ref "U1") (pin "66") (pinfunction "PCMIN_66") (pintype "input"))
    )
    (net (code "86") (name "unconnected-(U1-PCMOUT-Pad30)") (class "Default")
      (node (ref "U1") (pin "30") (pinfunction "PCMOUT_30") (pintype "output"))
    )
    (net (code "87") (name "unconnected-(U1-PCMSYNC-Pad65)") (class "Default")
      (node (ref "U1") (pin "65") (pinfunction "PCMSYNC_65") (pintype "output"))
    )
    (net (code "88") (name "unconnected-(U1-PWM-Pad26)") (class "Default")
      (node (ref "U1") (pin "26") (pinfunction "PWM_26") (pintype "output"))
    )
    (net (code "89") (name "unconnected-(U1-ROW0-Pad62)") (class "Default")
      (node (ref "U1") (pin "62") (pinfunction "ROW0_62") (pintype "bidirectional"))
    )
    (net (code "90") (name "unconnected-(U1-ROW1-Pad60)") (class "Default")
      (node (ref "U1") (pin "60") (pinfunction "ROW1_60") (pintype "bidirectional"))
    )
    (net (code "91") (name "unconnected-(U1-ROW2-Pad61)") (class "Default")
      (node (ref "U1") (pin "61") (pinfunction "ROW2_61") (pintype "bidirectional"))
    )
    (net (code "92") (name "unconnected-(U1-ROW3-Pad23)") (class "Default")
      (node (ref "U1") (pin "23") (pinfunction "ROW3_23") (pintype "bidirectional"))
    )
    (net (code "93") (name "unconnected-(U1-ROW4-Pad63)") (class "Default")
      (node (ref "U1") (pin "63") (pinfunction "ROW4_63") (pintype "bidirectional"))
    )
    (net (code "94") (name "unconnected-(U1-SCL-Pad74)") (class "Default")
      (node (ref "U1") (pin "74") (pinfunction "SCL_74") (pintype "bidirectional"))
    )
    (net (code "95") (name "unconnected-(U1-SDA-Pad75)") (class "Default")
      (node (ref "U1") (pin "75") (pinfunction "SDA_75") (pintype "bidirectional"))
    )
    (net (code "96") (name "unconnected-(U1-SIMPRE-Pad54)") (class "Default")
      (node (ref "U1") (pin "54") (pinfunction "SIMPRE_54") (pintype "input"))
    )
    (net (code "97") (name "unconnected-(U1-SPK1N-Pad13)") (class "Default")
      (node (ref "U1") (pin "13") (pinfunction "SPK1N_13") (pintype "output"))
    )
    (net (code "98") (name "unconnected-(U1-SPK1P-Pad53)") (class "Default")
      (node (ref "U1") (pin "53") (pinfunction "SPK1P_53") (pintype "output"))
    )
    (net (code "99") (name "unconnected-(U1-SPK2N-Pad11)") (class "Default")
      (node (ref "U1") (pin "11") (pinfunction "SPK2N_11") (pintype "output"))
    )
    (net (code "100") (name "unconnected-(U1-SPK2P{slash}8Ω-Pad51)") (class "Default")
      (node (ref "U1") (pin "51") (pinfunction "SPK2P/8Ω_51") (pintype "output"))
    )
    (net (code "101") (name "unconnected-(U1-UART_CTS-Pad34)") (class "Default")
      (node (ref "U1") (pin "34") (pinfunction "UART_CTS_34") (pintype "output"))
    )
    (net (code "102") (name "unconnected-(U1-UART_DCD-Pad70)") (class "Default")
      (node (ref "U1") (pin "70") (pinfunction "UART_DCD_70") (pintype "input"))
    )
    (net (code "103") (name "unconnected-(U1-UART_DTR-Pad69)") (class "Default")
      (node (ref "U1") (pin "69") (pinfunction "UART_DTR_69") (pintype "input"))
    )
    (net (code "104") (name "unconnected-(U1-UART_RTS-Pad33)") (class "Default")
      (node (ref "U1") (pin "33") (pinfunction "UART_RTS_33") (pintype "input"))
    )
    (net (code "105") (name "unconnected-(U1-USB_DM-Pad19)") (class "Default")
      (node (ref "U1") (pin "19") (pinfunction "USB_DM_19") (pintype "bidirectional"))
    )
    (net (code "106") (name "unconnected-(U1-USB_DP-Pad59)") (class "Default")
      (node (ref "U1") (pin "59") (pinfunction "USB_DP_59") (pintype "bidirectional"))
    )
    (net (code "107") (name "unconnected-(X1A-S-Pad1)") (class "Default")
      (node (ref "X1") (pin "1") (pinfunction "S_1") (pintype "passive"))
    )
    (net (code "108") (name "unconnected-(X1B-S-Pad2)") (class "Default")
      (node (ref "X1") (pin "2") (pinfunction "S_2") (pintype "passive"))
    )
    (net (code "109") (name "unconnected-(X1C-S-Pad3)") (class "Default")
      (node (ref "X1") (pin "3") (pinfunction "S_3") (pintype "passive"))
    )
    (net (code "110") (name "unconnected-(X1F-S-Pad6)") (class "Default")
      (node (ref "X1") (pin "6") (pinfunction "S_6") (pintype "passive"))
    )
    (net (code "111") (name "unconnected-(X2-5-PadC6)") (class "Default")
      (node (ref "X2") (pin "C6") (pinfunction "5_C6") (pintype "passive"))
    )
  )
)
